# biv2-LRcom_1a.net
KiCad netlist of a schematic drawn in Altium Designer
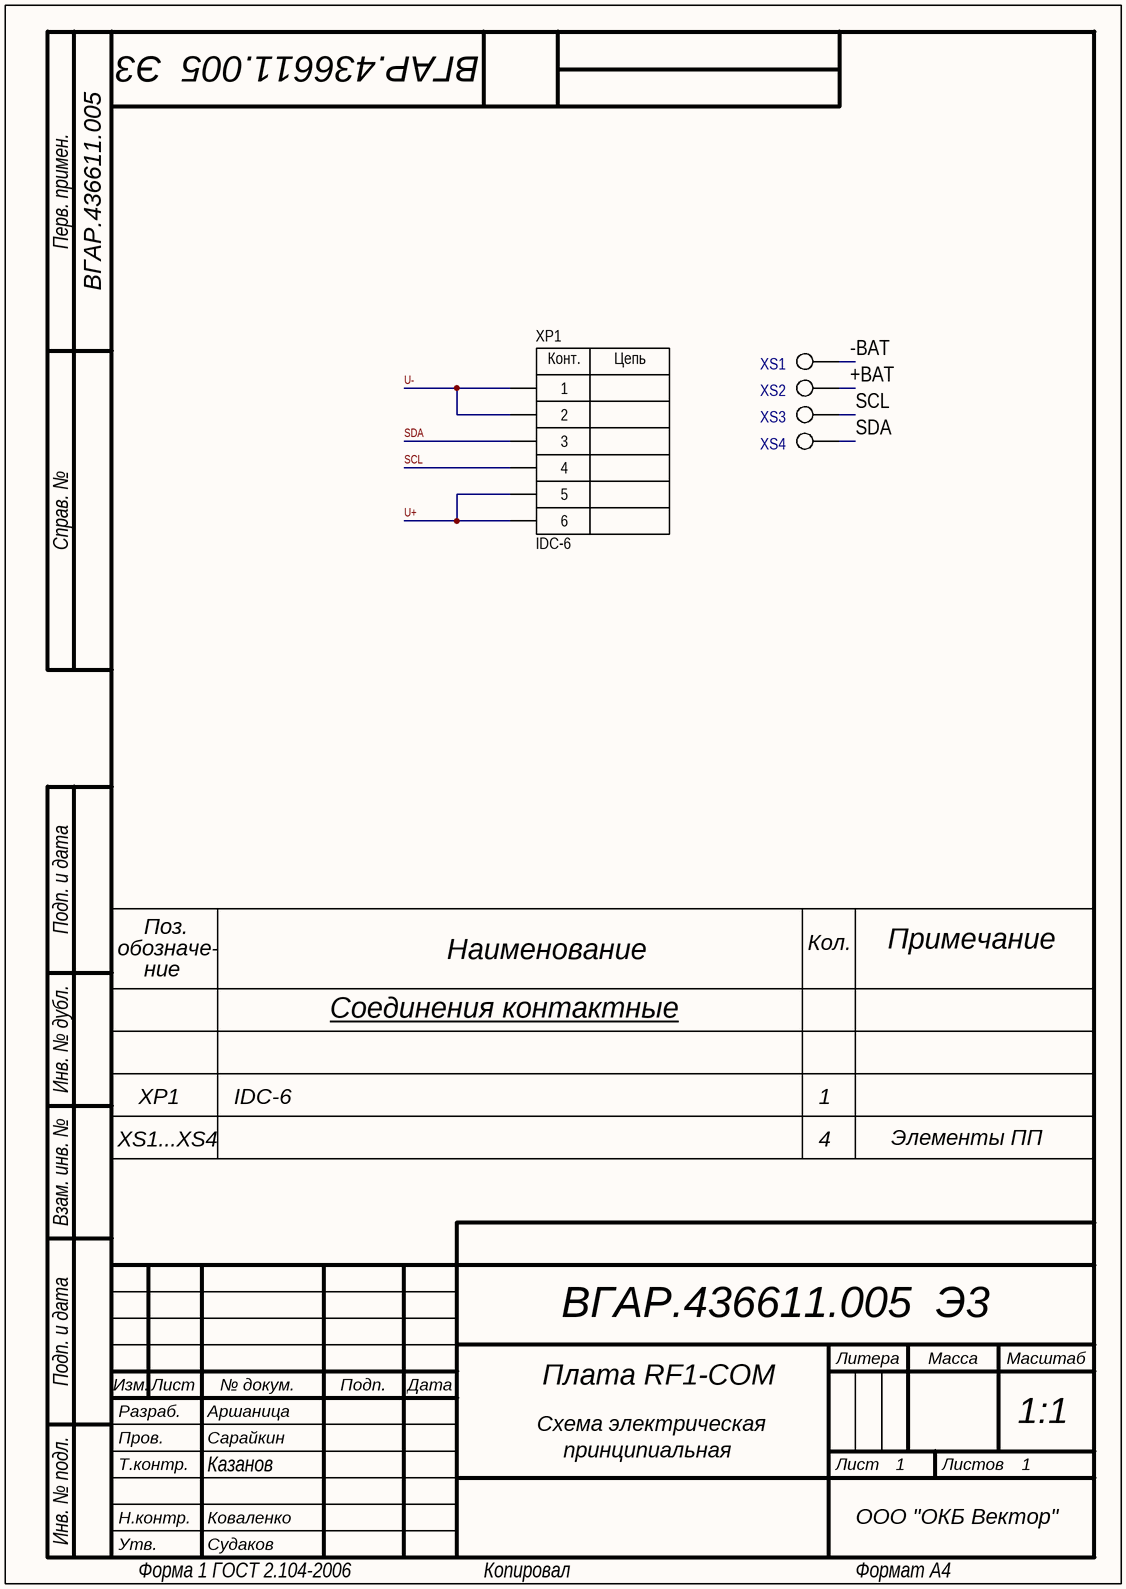
[diagram p0: biv2-LRcom_1a.SchDoc]

(export (version "E")
  (design (tool "Eeschema 10.0.6"))
  (components
    (comp (ref "XP1")
      (value "~")
      (footprint "CON: IDC-6MS")
      (fields
        (field (name "MANUFACTURER") "Connfly")
        (field (name "VALUEMANUFACTURERPARTNUMBER") "Connector, 6pin, 2.54mm, 250VAC, 3A")
        (field (name "PARTNUMBER") "IDC-6")
        (field (name "COMMENTTEXT") "IDC-6")
      )
      (libsource (lib "connector") (part "IDC-6"))
    )
    (comp (ref "XS1")
      (value "Testpoint_HS1mm")
      (footprint "TestPoint(without 3D)")
      (libsource (lib "connector") (part "Testpoint_HS1mm"))
    )
    (comp (ref "XS2")
      (value "Testpoint_HS1mm")
      (footprint "TestPoint(without 3D)")
      (libsource (lib "connector") (part "Testpoint_HS1mm"))
    )
    (comp (ref "XS3")
      (value "Testpoint_HS1mm")
      (footprint "TestPoint(without 3D)")
      (libsource (lib "connector") (part "Testpoint_HS1mm"))
    )
    (comp (ref "XS4")
      (value "Testpoint_HS1mm")
      (footprint "TestPoint(without 3D)")
      (libsource (lib "connector") (part "Testpoint_HS1mm"))
    )
  )
  (nets
    (net (code "1") (name "/SCL") (class "Default")
      (node (ref "XP1") (pin "4") (pinfunction "4_4") (pintype "power_in"))
    )
    (net (code "2") (name "/SDA") (class "Default")
      (node (ref "XP1") (pin "3") (pinfunction "3_3") (pintype "power_in"))
    )
    (net (code "3") (name "/U+") (class "Default")
      (node (ref "XP1") (pin "5") (pinfunction "5_5") (pintype "power_in"))
      (node (ref "XP1") (pin "6") (pinfunction "6_6") (pintype "power_in"))
    )
    (net (code "4") (name "/U-") (class "Default")
      (node (ref "XP1") (pin "1") (pinfunction "1_1") (pintype "passive"))
      (node (ref "XP1") (pin "2") (pinfunction "2_2") (pintype "passive"))
    )
    (net (code "5") (name "unconnected-(XS1-Pad1)") (class "Default")
      (node (ref "XS1") (pin "1") (pinfunction "1_1") (pintype "passive"))
    )
    (net (code "6") (name "unconnected-(XS2-Pad1)") (class "Default")
      (node (ref "XS2") (pin "1") (pinfunction "1_1") (pintype "passive"))
    )
    (net (code "7") (name "unconnected-(XS3-Pad1)") (class "Default")
      (node (ref "XS3") (pin "1") (pinfunction "1_1") (pintype "passive"))
    )
    (net (code "8") (name "unconnected-(XS4-Pad1)") (class "Default")
      (node (ref "XS4") (pin "1") (pinfunction "1_1") (pintype "passive"))
    )
  )
)
